# FPGA_Supply_Pins.net
KiCad netlist of a schematic drawn in Altium Designer
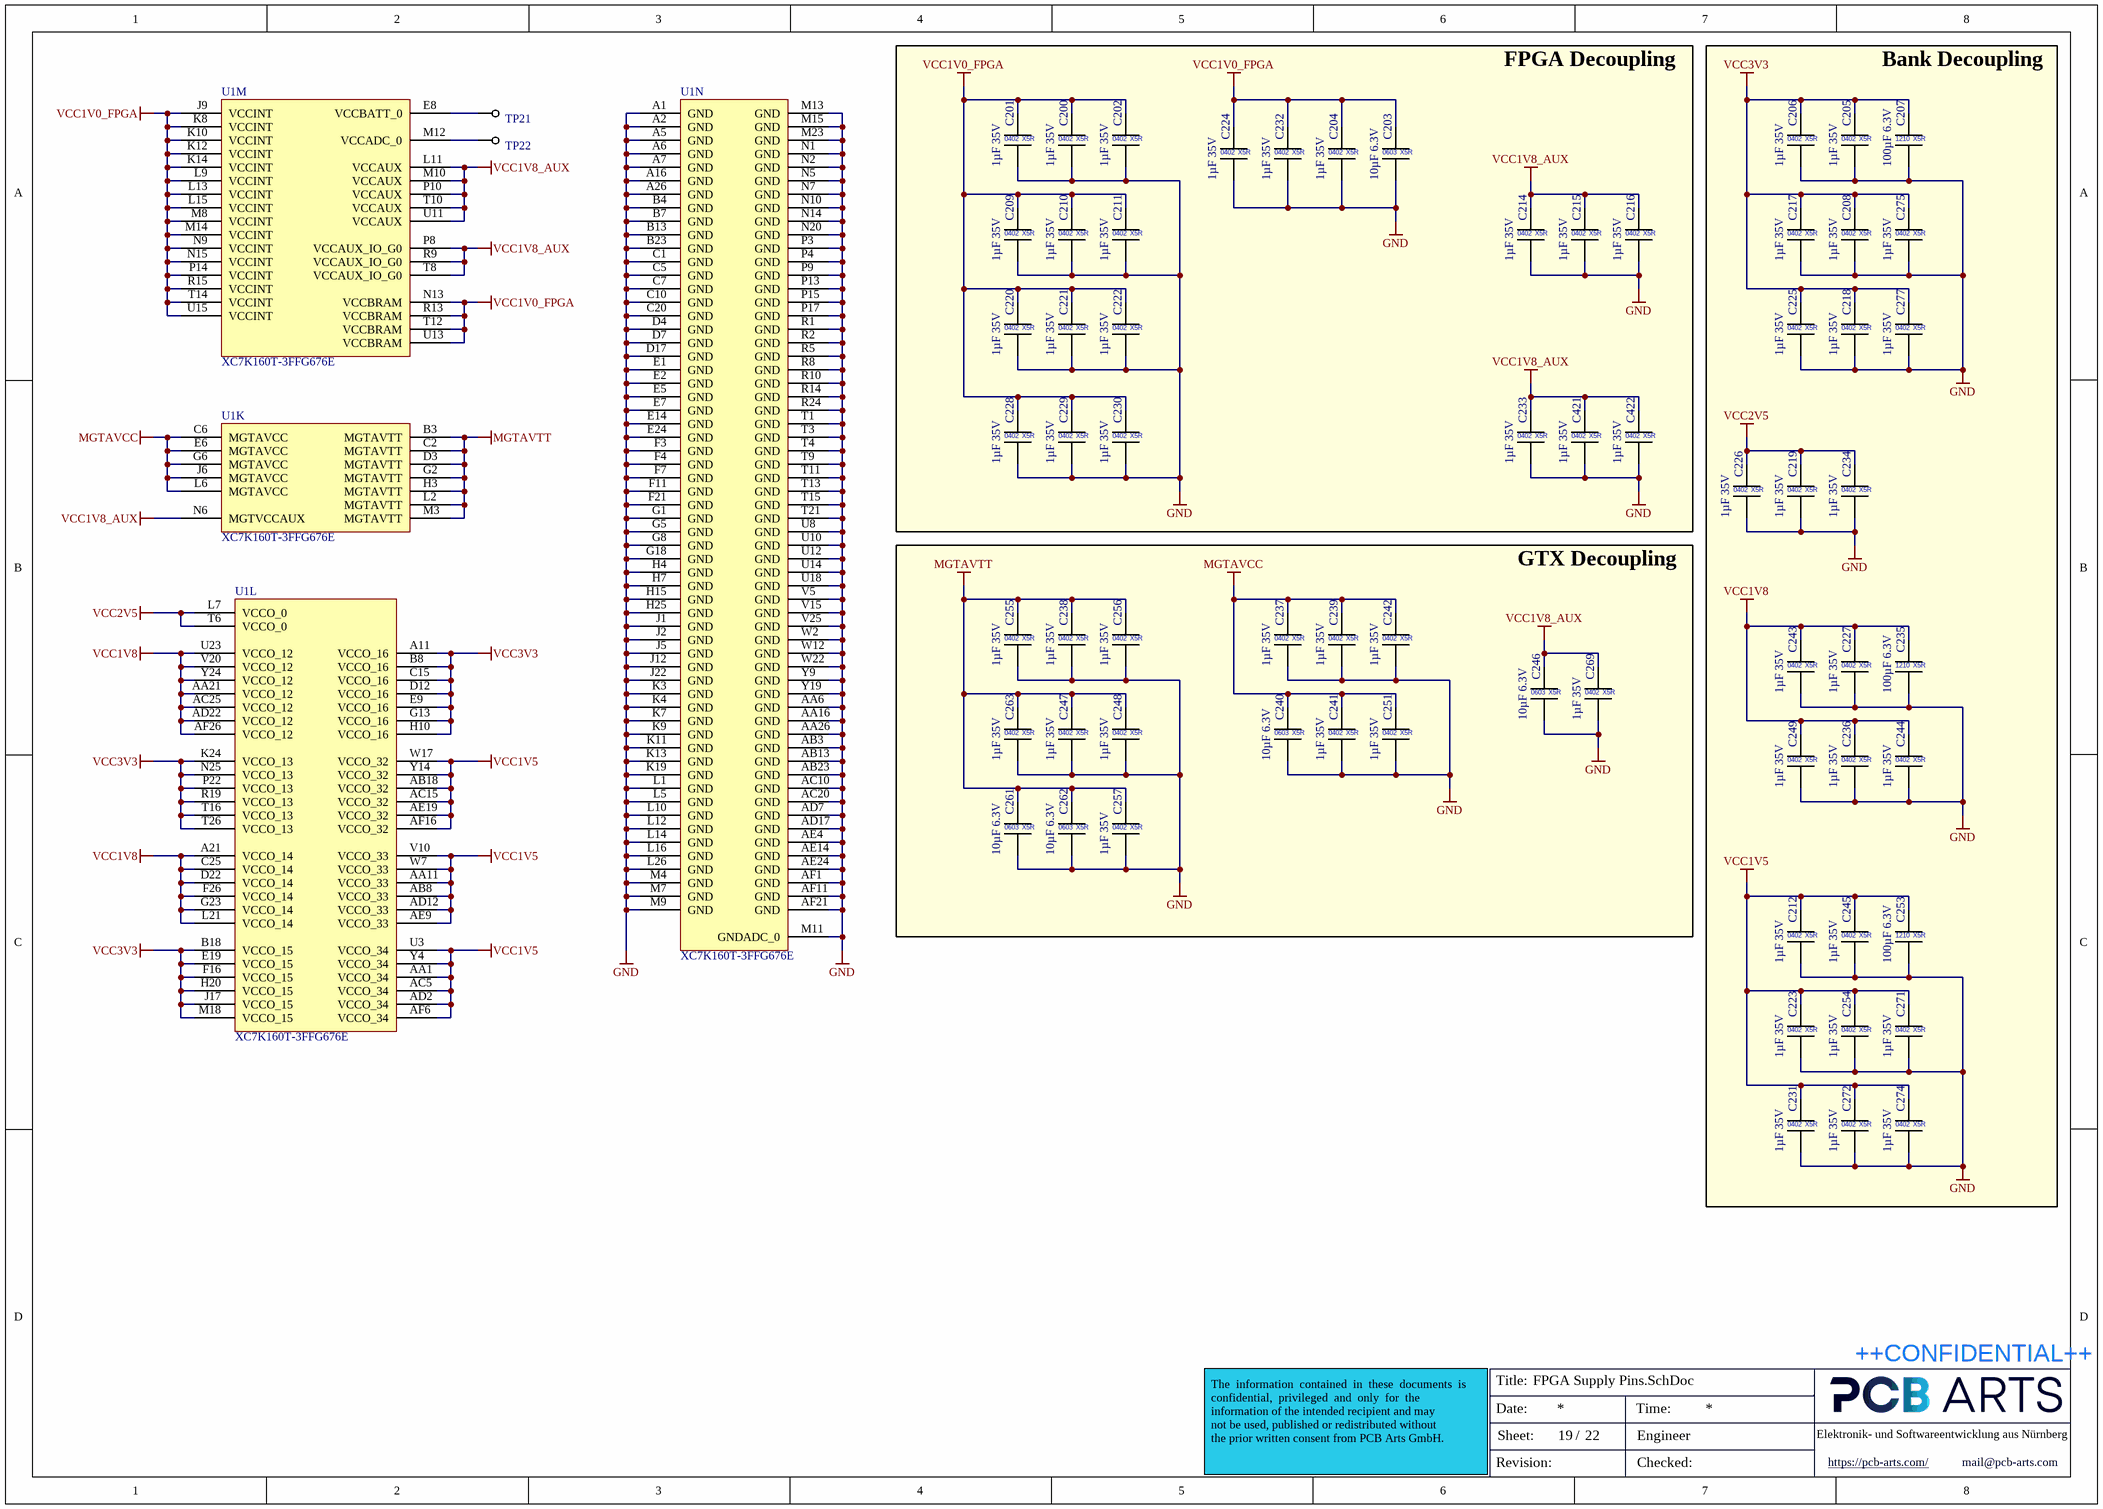
[diagram p0: FPGA Supply Pins.SchDoc]

(export (version "E")
  (design (tool "Eeschema 10.0.6"))
  (components
    (comp (ref "C200")
      (value "1µF 35V")
      (footprint "Cap:CAP_0402_L")
      (description "Multilayer Ceramic Capacitors MLCC - SMD/SMT 0402 35VDC")
      (libsource (lib "Cap") (part "CAP_0402_1µF_35V"))
    )
    (comp (ref "C201")
      (value "1µF 35V")
      (footprint "Cap:CAP_0402_L")
      (description "Multilayer Ceramic Capacitors MLCC - SMD/SMT 0402 35VDC")
      (libsource (lib "Cap") (part "CAP_0402_1µF_35V"))
    )
    (comp (ref "C202")
      (value "1µF 35V")
      (footprint "Cap:CAP_0402_L")
      (description "Multilayer Ceramic Capacitors MLCC - SMD/SMT 0402 35VDC")
      (libsource (lib "Cap") (part "CAP_0402_1µF_35V"))
    )
    (comp (ref "C203")
      (value "10µF 6.3V")
      (footprint "Cap:CAP_0603_L")
      (description "Multilayer Ceramic Capacitors MLCC - SMD/SMT 0603 6.3VDC")
      (libsource (lib "Cap") (part "CAP_0603_10µF_6.3V"))
    )
    (comp (ref "C204")
      (value "1µF 35V")
      (footprint "Cap:CAP_0402_L")
      (description "Multilayer Ceramic Capacitors MLCC - SMD/SMT 0402 35VDC")
      (libsource (lib "Cap") (part "CAP_0402_1µF_35V"))
    )
    (comp (ref "C205")
      (value "1µF 35V")
      (footprint "Cap:CAP_0402_L")
      (description "Multilayer Ceramic Capacitors MLCC - SMD/SMT 0402 35VDC")
      (libsource (lib "Cap") (part "CAP_0402_1µF_35V"))
    )
    (comp (ref "C206")
      (value "1µF 35V")
      (footprint "Cap:CAP_0402_L")
      (description "Multilayer Ceramic Capacitors MLCC - SMD/SMT 0402 35VDC")
      (libsource (lib "Cap") (part "CAP_0402_1µF_35V"))
    )
    (comp (ref "C207")
      (value "100µF 6.3V")
      (footprint "Cap:CAP_1210")
      (description "Multilayer Ceramic Capacitors MLCC - SMD/SMT 1210 6.3VDC")
      (libsource (lib "Cap") (part "CAP_1210_100µF_6.3V"))
    )
    (comp (ref "C208")
      (value "1µF 35V")
      (footprint "Cap:CAP_0402_L")
      (description "Multilayer Ceramic Capacitors MLCC - SMD/SMT 0402 35VDC")
      (libsource (lib "Cap") (part "CAP_0402_1µF_35V"))
    )
    (comp (ref "C209")
      (value "1µF 35V")
      (footprint "Cap:CAP_0402_L")
      (description "Multilayer Ceramic Capacitors MLCC - SMD/SMT 0402 35VDC")
      (libsource (lib "Cap") (part "CAP_0402_1µF_35V"))
    )
    (comp (ref "C210")
      (value "1µF 35V")
      (footprint "Cap:CAP_0402_L")
      (description "Multilayer Ceramic Capacitors MLCC - SMD/SMT 0402 35VDC")
      (libsource (lib "Cap") (part "CAP_0402_1µF_35V"))
    )
    (comp (ref "C211")
      (value "1µF 35V")
      (footprint "Cap:CAP_0402_L")
      (description "Multilayer Ceramic Capacitors MLCC - SMD/SMT 0402 35VDC")
      (libsource (lib "Cap") (part "CAP_0402_1µF_35V"))
    )
    (comp (ref "C212")
      (value "1µF 35V")
      (footprint "Cap:CAP_0402_L")
      (description "Multilayer Ceramic Capacitors MLCC - SMD/SMT 0402 35VDC")
      (libsource (lib "Cap") (part "CAP_0402_1µF_35V"))
    )
    (comp (ref "C214")
      (value "1µF 35V")
      (footprint "Cap:CAP_0402_L")
      (description "Multilayer Ceramic Capacitors MLCC - SMD/SMT 0402 35VDC")
      (libsource (lib "Cap") (part "CAP_0402_1µF_35V"))
    )
    (comp (ref "C215")
      (value "1µF 35V")
      (footprint "Cap:CAP_0402_L")
      (description "Multilayer Ceramic Capacitors MLCC - SMD/SMT 0402 35VDC")
      (libsource (lib "Cap") (part "CAP_0402_1µF_35V"))
    )
    (comp (ref "C216")
      (value "1µF 35V")
      (footprint "Cap:CAP_0402_L")
      (description "Multilayer Ceramic Capacitors MLCC - SMD/SMT 0402 35VDC")
      (libsource (lib "Cap") (part "CAP_0402_1µF_35V"))
    )
    (comp (ref "C217")
      (value "1µF 35V")
      (footprint "Cap:CAP_0402_L")
      (description "Multilayer Ceramic Capacitors MLCC - SMD/SMT 0402 35VDC")
      (libsource (lib "Cap") (part "CAP_0402_1µF_35V"))
    )
    (comp (ref "C218")
      (value "1µF 35V")
      (footprint "Cap:CAP_0402_L")
      (description "Multilayer Ceramic Capacitors MLCC - SMD/SMT 0402 35VDC")
      (libsource (lib "Cap") (part "CAP_0402_1µF_35V"))
    )
    (comp (ref "C219")
      (value "1µF 35V")
      (footprint "Cap:CAP_0402_L")
      (description "Multilayer Ceramic Capacitors MLCC - SMD/SMT 0402 35VDC")
      (libsource (lib "Cap") (part "CAP_0402_1µF_35V"))
    )
    (comp (ref "C220")
      (value "1µF 35V")
      (footprint "Cap:CAP_0402_L")
      (description "Multilayer Ceramic Capacitors MLCC - SMD/SMT 0402 35VDC")
      (libsource (lib "Cap") (part "CAP_0402_1µF_35V"))
    )
    (comp (ref "C221")
      (value "1µF 35V")
      (footprint "Cap:CAP_0402_L")
      (description "Multilayer Ceramic Capacitors MLCC - SMD/SMT 0402 35VDC")
      (libsource (lib "Cap") (part "CAP_0402_1µF_35V"))
    )
    (comp (ref "C222")
      (value "1µF 35V")
      (footprint "Cap:CAP_0402_L")
      (description "Multilayer Ceramic Capacitors MLCC - SMD/SMT 0402 35VDC")
      (libsource (lib "Cap") (part "CAP_0402_1µF_35V"))
    )
    (comp (ref "C223")
      (value "1µF 35V")
      (footprint "Cap:CAP_0402_L")
      (description "Multilayer Ceramic Capacitors MLCC - SMD/SMT 0402 35VDC")
      (libsource (lib "Cap") (part "CAP_0402_1µF_35V"))
    )
    (comp (ref "C224")
      (value "1µF 35V")
      (footprint "Cap:CAP_0402_L")
      (description "Multilayer Ceramic Capacitors MLCC - SMD/SMT 0402 35VDC")
      (libsource (lib "Cap") (part "CAP_0402_1µF_35V"))
    )
    (comp (ref "C225")
      (value "1µF 35V")
      (footprint "Cap:CAP_0402_L")
      (description "Multilayer Ceramic Capacitors MLCC - SMD/SMT 0402 35VDC")
      (libsource (lib "Cap") (part "CAP_0402_1µF_35V"))
    )
    (comp (ref "C226")
      (value "1µF 35V")
      (footprint "Cap:CAP_0402_L")
      (description "Multilayer Ceramic Capacitors MLCC - SMD/SMT 0402 35VDC")
      (libsource (lib "Cap") (part "CAP_0402_1µF_35V"))
    )
    (comp (ref "C227")
      (value "1µF 35V")
      (footprint "Cap:CAP_0402_L")
      (description "Multilayer Ceramic Capacitors MLCC - SMD/SMT 0402 35VDC")
      (libsource (lib "Cap") (part "CAP_0402_1µF_35V"))
    )
    (comp (ref "C228")
      (value "1µF 35V")
      (footprint "Cap:CAP_0402_L")
      (description "Multilayer Ceramic Capacitors MLCC - SMD/SMT 0402 35VDC")
      (libsource (lib "Cap") (part "CAP_0402_1µF_35V"))
    )
    (comp (ref "C229")
      (value "1µF 35V")
      (footprint "Cap:CAP_0402_L")
      (description "Multilayer Ceramic Capacitors MLCC - SMD/SMT 0402 35VDC")
      (libsource (lib "Cap") (part "CAP_0402_1µF_35V"))
    )
    (comp (ref "C230")
      (value "1µF 35V")
      (footprint "Cap:CAP_0402_L")
      (description "Multilayer Ceramic Capacitors MLCC - SMD/SMT 0402 35VDC")
      (libsource (lib "Cap") (part "CAP_0402_1µF_35V"))
    )
    (comp (ref "C231")
      (value "1µF 35V")
      (footprint "Cap:CAP_0402_L")
      (description "Multilayer Ceramic Capacitors MLCC - SMD/SMT 0402 35VDC")
      (libsource (lib "Cap") (part "CAP_0402_1µF_35V"))
    )
    (comp (ref "C232")
      (value "1µF 35V")
      (footprint "Cap:CAP_0402_L")
      (description "Multilayer Ceramic Capacitors MLCC - SMD/SMT 0402 35VDC")
      (libsource (lib "Cap") (part "CAP_0402_1µF_35V"))
    )
    (comp (ref "C233")
      (value "1µF 35V")
      (footprint "Cap:CAP_0402_L")
      (description "Multilayer Ceramic Capacitors MLCC - SMD/SMT 0402 35VDC")
      (libsource (lib "Cap") (part "CAP_0402_1µF_35V"))
    )
    (comp (ref "C234")
      (value "1µF 35V")
      (footprint "Cap:CAP_0402_L")
      (description "Multilayer Ceramic Capacitors MLCC - SMD/SMT 0402 35VDC")
      (libsource (lib "Cap") (part "CAP_0402_1µF_35V"))
    )
    (comp (ref "C235")
      (value "100µF 6.3V")
      (footprint "Cap:CAP_1210")
      (description "Multilayer Ceramic Capacitors MLCC - SMD/SMT 1210 6.3VDC")
      (libsource (lib "Cap") (part "CAP_1210_100µF_6.3V"))
    )
    (comp (ref "C236")
      (value "1µF 35V")
      (footprint "Cap:CAP_0402_L")
      (description "Multilayer Ceramic Capacitors MLCC - SMD/SMT 0402 35VDC")
      (libsource (lib "Cap") (part "CAP_0402_1µF_35V"))
    )
    (comp (ref "C237")
      (value "1µF 35V")
      (footprint "Cap:CAP_0402_L")
      (description "Multilayer Ceramic Capacitors MLCC - SMD/SMT 0402 35VDC")
      (libsource (lib "Cap") (part "CAP_0402_1µF_35V"))
    )
    (comp (ref "C238")
      (value "1µF 35V")
      (footprint "Cap:CAP_0402_L")
      (description "Multilayer Ceramic Capacitors MLCC - SMD/SMT 0402 35VDC")
      (libsource (lib "Cap") (part "CAP_0402_1µF_35V"))
    )
    (comp (ref "C239")
      (value "1µF 35V")
      (footprint "Cap:CAP_0402_L")
      (description "Multilayer Ceramic Capacitors MLCC - SMD/SMT 0402 35VDC")
      (libsource (lib "Cap") (part "CAP_0402_1µF_35V"))
    )
    (comp (ref "C240")
      (value "10µF 6.3V")
      (footprint "Cap:CAP_0603_L")
      (description "Multilayer Ceramic Capacitors MLCC - SMD/SMT 0603 6.3VDC")
      (libsource (lib "Cap") (part "CAP_0603_10µF_6.3V"))
    )
    (comp (ref "C241")
      (value "1µF 35V")
      (footprint "Cap:CAP_0402_L")
      (description "Multilayer Ceramic Capacitors MLCC - SMD/SMT 0402 35VDC")
      (libsource (lib "Cap") (part "CAP_0402_1µF_35V"))
    )
    (comp (ref "C242")
      (value "1µF 35V")
      (footprint "Cap:CAP_0402_L")
      (description "Multilayer Ceramic Capacitors MLCC - SMD/SMT 0402 35VDC")
      (libsource (lib "Cap") (part "CAP_0402_1µF_35V"))
    )
    (comp (ref "C243")
      (value "1µF 35V")
      (footprint "Cap:CAP_0402_L")
      (description "Multilayer Ceramic Capacitors MLCC - SMD/SMT 0402 35VDC")
      (libsource (lib "Cap") (part "CAP_0402_1µF_35V"))
    )
    (comp (ref "C244")
      (value "1µF 35V")
      (footprint "Cap:CAP_0402_L")
      (description "Multilayer Ceramic Capacitors MLCC - SMD/SMT 0402 35VDC")
      (libsource (lib "Cap") (part "CAP_0402_1µF_35V"))
    )
    (comp (ref "C245")
      (value "1µF 35V")
      (footprint "Cap:CAP_0402_L")
      (description "Multilayer Ceramic Capacitors MLCC - SMD/SMT 0402 35VDC")
      (libsource (lib "Cap") (part "CAP_0402_1µF_35V"))
    )
    (comp (ref "C246")
      (value "10µF 6.3V")
      (footprint "Cap:CAP_0603_L")
      (description "Multilayer Ceramic Capacitors MLCC - SMD/SMT 0603 6.3VDC")
      (libsource (lib "Cap") (part "CAP_0603_10µF_6.3V"))
    )
    (comp (ref "C247")
      (value "1µF 35V")
      (footprint "Cap:CAP_0402_L")
      (description "Multilayer Ceramic Capacitors MLCC - SMD/SMT 0402 35VDC")
      (libsource (lib "Cap") (part "CAP_0402_1µF_35V"))
    )
    (comp (ref "C248")
      (value "1µF 35V")
      (footprint "Cap:CAP_0402_L")
      (description "Multilayer Ceramic Capacitors MLCC - SMD/SMT 0402 35VDC")
      (libsource (lib "Cap") (part "CAP_0402_1µF_35V"))
    )
    (comp (ref "C249")
      (value "1µF 35V")
      (footprint "Cap:CAP_0402_L")
      (description "Multilayer Ceramic Capacitors MLCC - SMD/SMT 0402 35VDC")
      (libsource (lib "Cap") (part "CAP_0402_1µF_35V"))
    )
    (comp (ref "C251")
      (value "1µF 35V")
      (footprint "Cap:CAP_0402_L")
      (description "Multilayer Ceramic Capacitors MLCC - SMD/SMT 0402 35VDC")
      (libsource (lib "Cap") (part "CAP_0402_1µF_35V"))
    )
    (comp (ref "C253")
      (value "100µF 6.3V")
      (footprint "Cap:CAP_1210")
      (description "Multilayer Ceramic Capacitors MLCC - SMD/SMT 1210 6.3VDC")
      (libsource (lib "Cap") (part "CAP_1210_100µF_6.3V"))
    )
    (comp (ref "C254")
      (value "1µF 35V")
      (footprint "Cap:CAP_0402_L")
      (description "Multilayer Ceramic Capacitors MLCC - SMD/SMT 0402 35VDC")
      (libsource (lib "Cap") (part "CAP_0402_1µF_35V"))
    )
    (comp (ref "C255")
      (value "1µF 35V")
      (footprint "Cap:CAP_0402_L")
      (description "Multilayer Ceramic Capacitors MLCC - SMD/SMT 0402 35VDC")
      (libsource (lib "Cap") (part "CAP_0402_1µF_35V"))
    )
    (comp (ref "C256")
      (value "1µF 35V")
      (footprint "Cap:CAP_0402_L")
      (description "Multilayer Ceramic Capacitors MLCC - SMD/SMT 0402 35VDC")
      (libsource (lib "Cap") (part "CAP_0402_1µF_35V"))
    )
    (comp (ref "C257")
      (value "1µF 35V")
      (footprint "Cap:CAP_0402_L")
      (description "Multilayer Ceramic Capacitors MLCC - SMD/SMT 0402 35VDC")
      (libsource (lib "Cap") (part "CAP_0402_1µF_35V"))
    )
    (comp (ref "C261")
      (value "10µF 6.3V")
      (footprint "Cap:CAP_0603_L")
      (description "Multilayer Ceramic Capacitors MLCC - SMD/SMT 0603 6.3VDC")
      (libsource (lib "Cap") (part "CAP_0603_10µF_6.3V"))
    )
    (comp (ref "C262")
      (value "10µF 6.3V")
      (footprint "Cap:CAP_0603_L")
      (description "Multilayer Ceramic Capacitors MLCC - SMD/SMT 0603 6.3VDC")
      (libsource (lib "Cap") (part "CAP_0603_10µF_6.3V"))
    )
    (comp (ref "C263")
      (value "1µF 35V")
      (footprint "Cap:CAP_0402_L")
      (description "Multilayer Ceramic Capacitors MLCC - SMD/SMT 0402 35VDC")
      (libsource (lib "Cap") (part "CAP_0402_1µF_35V"))
    )
    (comp (ref "C269")
      (value "1µF 35V")
      (footprint "Cap:CAP_0402_L")
      (description "Multilayer Ceramic Capacitors MLCC - SMD/SMT 0402 35VDC")
      (libsource (lib "Cap") (part "CAP_0402_1µF_35V"))
    )
    (comp (ref "C271")
      (value "1µF 35V")
      (footprint "Cap:CAP_0402_L")
      (description "Multilayer Ceramic Capacitors MLCC - SMD/SMT 0402 35VDC")
      (libsource (lib "Cap") (part "CAP_0402_1µF_35V"))
    )
    (comp (ref "C272")
      (value "1µF 35V")
      (footprint "Cap:CAP_0402_L")
      (description "Multilayer Ceramic Capacitors MLCC - SMD/SMT 0402 35VDC")
      (libsource (lib "Cap") (part "CAP_0402_1µF_35V"))
    )
    (comp (ref "C274")
      (value "1µF 35V")
      (footprint "Cap:CAP_0402_L")
      (description "Multilayer Ceramic Capacitors MLCC - SMD/SMT 0402 35VDC")
      (libsource (lib "Cap") (part "CAP_0402_1µF_35V"))
    )
    (comp (ref "C275")
      (value "1µF 35V")
      (footprint "Cap:CAP_0402_L")
      (description "Multilayer Ceramic Capacitors MLCC - SMD/SMT 0402 35VDC")
      (libsource (lib "Cap") (part "CAP_0402_1µF_35V"))
    )
    (comp (ref "C277")
      (value "1µF 35V")
      (footprint "Cap:CAP_0402_L")
      (description "Multilayer Ceramic Capacitors MLCC - SMD/SMT 0402 35VDC")
      (libsource (lib "Cap") (part "CAP_0402_1µF_35V"))
    )
    (comp (ref "C421")
      (value "1µF 35V")
      (footprint "Cap:CAP_0402_L")
      (description "Multilayer Ceramic Capacitors MLCC - SMD/SMT 0402 35VDC")
      (libsource (lib "Cap") (part "CAP_0402_1µF_35V"))
    )
    (comp (ref "C422")
      (value "1µF 35V")
      (footprint "Cap:CAP_0402_L")
      (description "Multilayer Ceramic Capacitors MLCC - SMD/SMT 0402 35VDC")
      (libsource (lib "Cap") (part "CAP_0402_1µF_35V"))
    )
    (comp (ref "TP21")
      (value "Testpoint")
      (footprint "Electro_mech:Testpoint 0.8mm")
      (description "Testpoint 0.8mm")
      (libsource (lib "Electro_Mech") (part "Testpoint 0.8mm"))
    )
    (comp (ref "TP22")
      (value "Testpoint")
      (footprint "Electro_mech:Testpoint 0.8mm")
      (description "Testpoint 0.8mm")
      (libsource (lib "Electro_Mech") (part "Testpoint 0.8mm"))
    )
    (comp (ref "U1")
      (value "XC7K160T-3FFG676E")
      (footprint "Digital:BGA100P2700X2700X317-676N")
      (description "Kintex-7 FPGA, 400 User I/Os, 8 GTX, 676-Ball BGA, Speed Grade 3, Extended Grade, Pb-Free")
      (libsource (lib "Digital") (part "XC7K160T-3FFG676E_Kintex-7 FPGA, 400 User I/Os, 8 GTX, FFG676"))
    )
  )
  (nets
    (net (code "1") (name "GND") (class "Default")
      (node (ref "C200") (pin "2") (pinfunction "2_2") (pintype "passive"))
      (node (ref "C201") (pin "2") (pinfunction "2_2") (pintype "passive"))
      (node (ref "C202") (pin "2") (pinfunction "2_2") (pintype "passive"))
      (node (ref "C203") (pin "2") (pinfunction "2_2") (pintype "passive"))
      (node (ref "C204") (pin "2") (pinfunction "2_2") (pintype "passive"))
      (node (ref "C205") (pin "2") (pinfunction "2_2") (pintype "passive"))
      (node (ref "C206") (pin "2") (pinfunction "2_2") (pintype "passive"))
      (node (ref "C207") (pin "2") (pinfunction "2_2") (pintype "passive"))
      (node (ref "C208") (pin "2") (pinfunction "2_2") (pintype "passive"))
      (node (ref "C209") (pin "2") (pinfunction "2_2") (pintype "passive"))
      (node (ref "C210") (pin "2") (pinfunction "2_2") (pintype "passive"))
      (node (ref "C211") (pin "2") (pinfunction "2_2") (pintype "passive"))
      (node (ref "C212") (pin "2") (pinfunction "2_2") (pintype "passive"))
      (node (ref "C214") (pin "2") (pinfunction "2_2") (pintype "passive"))
      (node (ref "C215") (pin "2") (pinfunction "2_2") (pintype "passive"))
      (node (ref "C216") (pin "2") (pinfunction "2_2") (pintype "passive"))
      (node (ref "C217") (pin "2") (pinfunction "2_2") (pintype "passive"))
      (node (ref "C218") (pin "2") (pinfunction "2_2") (pintype "passive"))
      (node (ref "C219") (pin "2") (pinfunction "2_2") (pintype "passive"))
      (node (ref "C220") (pin "2") (pinfunction "2_2") (pintype "passive"))
      (node (ref "C221") (pin "2") (pinfunction "2_2") (pintype "passive"))
      (node (ref "C222") (pin "2") (pinfunction "2_2") (pintype "passive"))
      (node (ref "C223") (pin "2") (pinfunction "2_2") (pintype "passive"))
      (node (ref "C224") (pin "2") (pinfunction "2_2") (pintype "passive"))
      (node (ref "C225") (pin "2") (pinfunction "2_2") (pintype "passive"))
      (node (ref "C226") (pin "2") (pinfunction "2_2") (pintype "passive"))
      (node (ref "C227") (pin "2") (pinfunction "2_2") (pintype "passive"))
      (node (ref "C228") (pin "2") (pinfunction "2_2") (pintype "passive"))
      (node (ref "C229") (pin "2") (pinfunction "2_2") (pintype "passive"))
      (node (ref "C230") (pin "2") (pinfunction "2_2") (pintype "passive"))
      (node (ref "C231") (pin "2") (pinfunction "2_2") (pintype "passive"))
      (node (ref "C232") (pin "2") (pinfunction "2_2") (pintype "passive"))
      (node (ref "C233") (pin "2") (pinfunction "2_2") (pintype "passive"))
      (node (ref "C234") (pin "2") (pinfunction "2_2") (pintype "passive"))
      (node (ref "C235") (pin "2") (pinfunction "2_2") (pintype "passive"))
      (node (ref "C236") (pin "2") (pinfunction "2_2") (pintype "passive"))
      (node (ref "C237") (pin "2") (pinfunction "2_2") (pintype "passive"))
      (node (ref "C238") (pin "2") (pinfunction "2_2") (pintype "passive"))
      (node (ref "C239") (pin "2") (pinfunction "2_2") (pintype "passive"))
      (node (ref "C240") (pin "2") (pinfunction "2_2") (pintype "passive"))
      (node (ref "C241") (pin "2") (pinfunction "2_2") (pintype "passive"))
      (node (ref "C242") (pin "2") (pinfunction "2_2") (pintype "passive"))
      (node (ref "C243") (pin "2") (pinfunction "2_2") (pintype "passive"))
      (node (ref "C244") (pin "2") (pinfunction "2_2") (pintype "passive"))
      (node (ref "C245") (pin "2") (pinfunction "2_2") (pintype "passive"))
      (node (ref "C246") (pin "2") (pinfunction "2_2") (pintype "passive"))
      (node (ref "C247") (pin "2") (pinfunction "2_2") (pintype "passive"))
      (node (ref "C248") (pin "2") (pinfunction "2_2") (pintype "passive"))
      (node (ref "C249") (pin "2") (pinfunction "2_2") (pintype "passive"))
      (node (ref "C251") (pin "2") (pinfunction "2_2") (pintype "passive"))
      (node (ref "C253") (pin "2") (pinfunction "2_2") (pintype "passive"))
      (node (ref "C254") (pin "2") (pinfunction "2_2") (pintype "passive"))
      (node (ref "C255") (pin "2") (pinfunction "2_2") (pintype "passive"))
      (node (ref "C256") (pin "2") (pinfunction "2_2") (pintype "passive"))
      (node (ref "C257") (pin "2") (pinfunction "2_2") (pintype "passive"))
      (node (ref "C261") (pin "2") (pinfunction "2_2") (pintype "passive"))
      (node (ref "C262") (pin "2") (pinfunction "2_2") (pintype "passive"))
      (node (ref "C263") (pin "2") (pinfunction "2_2") (pintype "passive"))
      (node (ref "C269") (pin "2") (pinfunction "2_2") (pintype "passive"))
      (node (ref "C271") (pin "2") (pinfunction "2_2") (pintype "passive"))
      (node (ref "C272") (pin "2") (pinfunction "2_2") (pintype "passive"))
      (node (ref "C274") (pin "2") (pinfunction "2_2") (pintype "passive"))
      (node (ref "C275") (pin "2") (pinfunction "2_2") (pintype "passive"))
      (node (ref "C277") (pin "2") (pinfunction "2_2") (pintype "passive"))
      (node (ref "C421") (pin "2") (pinfunction "2_2") (pintype "passive"))
      (node (ref "C422") (pin "2") (pinfunction "2_2") (pintype "passive"))
      (node (ref "U1") (pin "A1") (pinfunction "GND_A1") (pintype "power_in"))
      (node (ref "U1") (pin "A16") (pinfunction "GND_A16") (pintype "power_in"))
      (node (ref "U1") (pin "A2") (pinfunction "GND_A2") (pintype "power_in"))
      (node (ref "U1") (pin "A26") (pinfunction "GND_A26") (pintype "power_in"))
      (node (ref "U1") (pin "A5") (pinfunction "GND_A5") (pintype "power_in"))
      (node (ref "U1") (pin "A6") (pinfunction "GND_A6") (pintype "power_in"))
      (node (ref "U1") (pin "A7") (pinfunction "GND_A7") (pintype "power_in"))
      (node (ref "U1") (pin "AA16") (pinfunction "GND_AA16") (pintype "power_in"))
      (node (ref "U1") (pin "AA26") (pinfunction "GND_AA26") (pintype "power_in"))
      (node (ref "U1") (pin "AA6") (pinfunction "GND_AA6") (pintype "power_in"))
      (node (ref "U1") (pin "AB13") (pinfunction "GND_AB13") (pintype "power_in"))
      (node (ref "U1") (pin "AB23") (pinfunction "GND_AB23") (pintype "power_in"))
      (node (ref "U1") (pin "AB3") (pinfunction "GND_AB3") (pintype "power_in"))
      (node (ref "U1") (pin "AC10") (pinfunction "GND_AC10") (pintype "power_in"))
      (node (ref "U1") (pin "AC20") (pinfunction "GND_AC20") (pintype "power_in"))
      (node (ref "U1") (pin "AD17") (pinfunction "GND_AD17") (pintype "power_in"))
      (node (ref "U1") (pin "AD7") (pinfunction "GND_AD7") (pintype "power_in"))
      (node (ref "U1") (pin "AE14") (pinfunction "GND_AE14") (pintype "power_in"))
      (node (ref "U1") (pin "AE24") (pinfunction "GND_AE24") (pintype "power_in"))
      (node (ref "U1") (pin "AE4") (pinfunction "GND_AE4") (pintype "power_in"))
      (node (ref "U1") (pin "AF1") (pinfunction "GND_AF1") (pintype "power_in"))
      (node (ref "U1") (pin "AF11") (pinfunction "GND_AF11") (pintype "power_in"))
      (node (ref "U1") (pin "AF21") (pinfunction "GND_AF21") (pintype "power_in"))
      (node (ref "U1") (pin "B13") (pinfunction "GND_B13") (pintype "power_in"))
      (node (ref "U1") (pin "B23") (pinfunction "GND_B23") (pintype "power_in"))
      (node (ref "U1") (pin "B4") (pinfunction "GND_B4") (pintype "power_in"))
      (node (ref "U1") (pin "B7") (pinfunction "GND_B7") (pintype "power_in"))
      (node (ref "U1") (pin "C1") (pinfunction "GND_C1") (pintype "power_in"))
      (node (ref "U1") (pin "C10") (pinfunction "GND_C10") (pintype "power_in"))
      (node (ref "U1") (pin "C20") (pinfunction "GND_C20") (pintype "power_in"))
      (node (ref "U1") (pin "C5") (pinfunction "GND_C5") (pintype "power_in"))
      (node (ref "U1") (pin "C7") (pinfunction "GND_C7") (pintype "power_in"))
      (node (ref "U1") (pin "D17") (pinfunction "GND_D17") (pintype "power_in"))
      (node (ref "U1") (pin "D4") (pinfunction "GND_D4") (pintype "power_in"))
      (node (ref "U1") (pin "D7") (pinfunction "GND_D7") (pintype "power_in"))
      (node (ref "U1") (pin "E1") (pinfunction "GND_E1") (pintype "power_in"))
      (node (ref "U1") (pin "E14") (pinfunction "GND_E14") (pintype "power_in"))
      (node (ref "U1") (pin "E2") (pinfunction "GND_E2") (pintype "power_in"))
      (node (ref "U1") (pin "E24") (pinfunction "GND_E24") (pintype "power_in"))
      (node (ref "U1") (pin "E5") (pinfunction "GND_E5") (pintype "power_in"))
      (node (ref "U1") (pin "E7") (pinfunction "GND_E7") (pintype "power_in"))
      (node (ref "U1") (pin "F11") (pinfunction "GND_F11") (pintype "power_in"))
      (node (ref "U1") (pin "F21") (pinfunction "GND_F21") (pintype "power_in"))
      (node (ref "U1") (pin "F3") (pinfunction "GND_F3") (pintype "power_in"))
      (node (ref "U1") (pin "F4") (pinfunction "GND_F4") (pintype "power_in"))
      (node (ref "U1") (pin "F7") (pinfunction "GND_F7") (pintype "power_in"))
      (node (ref "U1") (pin "G1") (pinfunction "GND_G1") (pintype "power_in"))
      (node (ref "U1") (pin "G18") (pinfunction "GND_G18") (pintype "power_in"))
      (node (ref "U1") (pin "G5") (pinfunction "GND_G5") (pintype "power_in"))
      (node (ref "U1") (pin "G8") (pinfunction "GND_G8") (pintype "power_in"))
      (node (ref "U1") (pin "H15") (pinfunction "GND_H15") (pintype "power_in"))
      (node (ref "U1") (pin "H25") (pinfunction "GND_H25") (pintype "power_in"))
      (node (ref "U1") (pin "H4") (pinfunction "GND_H4") (pintype "power_in"))
      (node (ref "U1") (pin "H7") (pinfunction "GND_H7") (pintype "power_in"))
      (node (ref "U1") (pin "J1") (pinfunction "GND_J1") (pintype "power_in"))
      (node (ref "U1") (pin "J12") (pinfunction "GND_J12") (pintype "power_in"))
      (node (ref "U1") (pin "J2") (pinfunction "GND_J2") (pintype "power_in"))
      (node (ref "U1") (pin "J22") (pinfunction "GND_J22") (pintype "power_in"))
      (node (ref "U1") (pin "J5") (pinfunction "GND_J5") (pintype "power_in"))
      (node (ref "U1") (pin "K11") (pinfunction "GND_K11") (pintype "power_in"))
      (node (ref "U1") (pin "K13") (pinfunction "GND_K13") (pintype "power_in"))
      (node (ref "U1") (pin "K19") (pinfunction "GND_K19") (pintype "power_in"))
      (node (ref "U1") (pin "K3") (pinfunction "GND_K3") (pintype "power_in"))
      (node (ref "U1") (pin "K4") (pinfunction "GND_K4") (pintype "power_in"))
      (node (ref "U1") (pin "K7") (pinfunction "GND_K7") (pintype "power_in"))
      (node (ref "U1") (pin "K9") (pinfunction "GND_K9") (pintype "power_in"))
      (node (ref "U1") (pin "L1") (pinfunction "GND_L1") (pintype "power_in"))
      (node (ref "U1") (pin "L10") (pinfunction "GND_L10") (pintype "power_in"))
      (node (ref "U1") (pin "L12") (pinfunction "GND_L12") (pintype "power_in"))
      (node (ref "U1") (pin "L14") (pinfunction "GND_L14") (pintype "power_in"))
      (node (ref "U1") (pin "L16") (pinfunction "GND_L16") (pintype "power_in"))
      (node (ref "U1") (pin "L26") (pinfunction "GND_L26") (pintype "power_in"))
      (node (ref "U1") (pin "L5") (pinfunction "GND_L5") (pintype "power_in"))
      (node (ref "U1") (pin "M11") (pinfunction "GNDADC_0_M11") (pintype "power_in"))
      (node (ref "U1") (pin "M13") (pinfunction "GND_M13") (pintype "power_in"))
      (node (ref "U1") (pin "M15") (pinfunction "GND_M15") (pintype "power_in"))
      (node (ref "U1") (pin "M23") (pinfunction "GND_M23") (pintype "power_in"))
      (node (ref "U1") (pin "M4") (pinfunction "GND_M4") (pintype "power_in"))
      (node (ref "U1") (pin "M7") (pinfunction "GND_M7") (pintype "power_in"))
      (node (ref "U1") (pin "M9") (pinfunction "GND_M9") (pintype "power_in"))
      (node (ref "U1") (pin "N1") (pinfunction "GND_N1") (pintype "power_in"))
      (node (ref "U1") (pin "N10") (pinfunction "GND_N10") (pintype "power_in"))
      (node (ref "U1") (pin "N14") (pinfunction "GND_N14") (pintype "power_in"))
      (node (ref "U1") (pin "N2") (pinfunction "GND_N2") (pintype "power_in"))
      (node (ref "U1") (pin "N20") (pinfunction "GND_N20") (pintype "power_in"))
      (node (ref "U1") (pin "N5") (pinfunction "GND_N5") (pintype "power_in"))
      (node (ref "U1") (pin "N7") (pinfunction "GND_N7") (pintype "power_in"))
      (node (ref "U1") (pin "P13") (pinfunction "GND_P13") (pintype "power_in"))
      (node (ref "U1") (pin "P15") (pinfunction "GND_P15") (pintype "power_in"))
      (node (ref "U1") (pin "P17") (pinfunction "GND_P17") (pintype "power_in"))
      (node (ref "U1") (pin "P3") (pinfunction "GND_P3") (pintype "power_in"))
      (node (ref "U1") (pin "P4") (pinfunction "GND_P4") (pintype "power_in"))
      (node (ref "U1") (pin "P9") (pinfunction "GND_P9") (pintype "power_in"))
      (node (ref "U1") (pin "R1") (pinfunction "GND_R1") (pintype "power_in"))
      (node (ref "U1") (pin "R10") (pinfunction "GND_R10") (pintype "power_in"))
      (node (ref "U1") (pin "R14") (pinfunction "GND_R14") (pintype "power_in"))
      (node (ref "U1") (pin "R2") (pinfunction "GND_R2") (pintype "power_in"))
      (node (ref "U1") (pin "R24") (pinfunction "GND_R24") (pintype "power_in"))
      (node (ref "U1") (pin "R5") (pinfunction "GND_R5") (pintype "power_in"))
      (node (ref "U1") (pin "R8") (pinfunction "GND_R8") (pintype "power_in"))
      (node (ref "U1") (pin "T1") (pinfunction "GND_T1") (pintype "power_in"))
      (node (ref "U1") (pin "T11") (pinfunction "GND_T11") (pintype "power_in"))
      (node (ref "U1") (pin "T13") (pinfunction "GND_T13") (pintype "power_in"))
      (node (ref "U1") (pin "T15") (pinfunction "GND_T15") (pintype "power_in"))
      (node (ref "U1") (pin "T21") (pinfunction "GND_T21") (pintype "power_in"))
      (node (ref "U1") (pin "T3") (pinfunction "GND_T3") (pintype "power_in"))
      (node (ref "U1") (pin "T4") (pinfunction "GND_T4") (pintype "power_in"))
      (node (ref "U1") (pin "T9") (pinfunction "GND_T9") (pintype "power_in"))
      (node (ref "U1") (pin "U10") (pinfunction "GND_U10") (pintype "power_in"))
      (node (ref "U1") (pin "U12") (pinfunction "GND_U12") (pintype "power_in"))
      (node (ref "U1") (pin "U14") (pinfunction "GND_U14") (pintype "power_in"))
      (node (ref "U1") (pin "U18") (pinfunction "GND_U18") (pintype "power_in"))
      (node (ref "U1") (pin "U8") (pinfunction "GND_U8") (pintype "power_in"))
      (node (ref "U1") (pin "V15") (pinfunction "GND_V15") (pintype "power_in"))
      (node (ref "U1") (pin "V25") (pinfunction "GND_V25") (pintype "power_in"))
      (node (ref "U1") (pin "V5") (pinfunction "GND_V5") (pintype "power_in"))
      (node (ref "U1") (pin "W12") (pinfunction "GND_W12") (pintype "power_in"))
      (node (ref "U1") (pin "W2") (pinfunction "GND_W2") (pintype "power_in"))
      (node (ref "U1") (pin "W22") (pinfunction "GND_W22") (pintype "power_in"))
      (node (ref "U1") (pin "Y19") (pinfunction "GND_Y19") (pintype "power_in"))
      (node (ref "U1") (pin "Y9") (pinfunction "GND_Y9") (pintype "power_in"))
    )
    (net (code "2") (name "MGTAVCC") (class "Default")
      (node (ref "C237") (pin "1") (pinfunction "1_1") (pintype "passive"))
      (node (ref "C239") (pin "1") (pinfunction "1_1") (pintype "passive"))
      (node (ref "C240") (pin "1") (pinfunction "1_1") (pintype "passive"))
      (node (ref "C241") (pin "1") (pinfunction "1_1") (pintype "passive"))
      (node (ref "C242") (pin "1") (pinfunction "1_1") (pintype "passive"))
      (node (ref "C251") (pin "1") (pinfunction "1_1") (pintype "passive"))
      (node (ref "U1") (pin "C6") (pinfunction "MGTAVCC_C6") (pintype "power_in"))
      (node (ref "U1") (pin "E6") (pinfunction "MGTAVCC_E6") (pintype "power_in"))
      (node (ref "U1") (pin "G6") (pinfunction "MGTAVCC_G6") (pintype "power_in"))
      (node (ref "U1") (pin "J6") (pinfunction "MGTAVCC_J6") (pintype "power_in"))
      (node (ref "U1") (pin "L6") (pinfunction "MGTAVCC_L6") (pintype "power_in"))
    )
    (net (code "3") (name "MGTAVTT") (class "Default")
      (node (ref "C238") (pin "1") (pinfunction "1_1") (pintype "passive"))
      (node (ref "C247") (pin "1") (pinfunction "1_1") (pintype "passive"))
      (node (ref "C248") (pin "1") (pinfunction "1_1") (pintype "passive"))
      (node (ref "C255") (pin "1") (pinfunction "1_1") (pintype "passive"))
      (node (ref "C256") (pin "1") (pinfunction "1_1") (pintype "passive"))
      (node (ref "C257") (pin "1") (pinfunction "1_1") (pintype "passive"))
      (node (ref "C261") (pin "1") (pinfunction "1_1") (pintype "passive"))
      (node (ref "C262") (pin "1") (pinfunction "1_1") (pintype "passive"))
      (node (ref "C263") (pin "1") (pinfunction "1_1") (pintype "passive"))
      (node (ref "U1") (pin "B3") (pinfunction "MGTAVTT_B3") (pintype "power_in"))
      (node (ref "U1") (pin "C2") (pinfunction "MGTAVTT_C2") (pintype "power_in"))
      (node (ref "U1") (pin "D3") (pinfunction "MGTAVTT_D3") (pintype "power_in"))
      (node (ref "U1") (pin "G2") (pinfunction "MGTAVTT_G2") (pintype "power_in"))
      (node (ref "U1") (pin "H3") (pinfunction "MGTAVTT_H3") (pintype "power_in"))
      (node (ref "U1") (pin "L2") (pinfunction "MGTAVTT_L2") (pintype "power_in"))
      (node (ref "U1") (pin "M3") (pinfunction "MGTAVTT_M3") (pintype "power_in"))
    )
    (net (code "4") (name "Net-(TP21-GND)") (class "Default")
      (node (ref "TP21") (pin "1") (pinfunction "GND_1") (pintype "passive"))
      (node (ref "U1") (pin "E8") (pinfunction "VCCBATT_0_E8") (pintype "power_in"))
    )
    (net (code "5") (name "Net-(TP22-GND)") (class "Default")
      (node (ref "TP22") (pin "1") (pinfunction "GND_1") (pintype "passive"))
      (node (ref "U1") (pin "M12") (pinfunction "VCCADC_0_M12") (pintype "power_in"))
    )
    (net (code "6") (name "VCC1V0_FPGA") (class "Default")
      (node (ref "C200") (pin "1") (pinfunction "1_1") (pintype "passive"))
      (node (ref "C201") (pin "1") (pinfunction "1_1") (pintype "passive"))
      (node (ref "C202") (pin "1") (pinfunction "1_1") (pintype "passive"))
      (node (ref "C203") (pin "1") (pinfunction "1_1") (pintype "passive"))
      (node (ref "C204") (pin "1") (pinfunction "1_1") (pintype "passive"))
      (node (ref "C209") (pin "1") (pinfunction "1_1") (pintype "passive"))
      (node (ref "C210") (pin "1") (pinfunction "1_1") (pintype "passive"))
      (node (ref "C211") (pin "1") (pinfunction "1_1") (pintype "passive"))
      (node (ref "C220") (pin "1") (pinfunction "1_1") (pintype "passive"))
      (node (ref "C221") (pin "1") (pinfunction "1_1") (pintype "passive"))
      (node (ref "C222") (pin "1") (pinfunction "1_1") (pintype "passive"))
      (node (ref "C224") (pin "1") (pinfunction "1_1") (pintype "passive"))
      (node (ref "C228") (pin "1") (pinfunction "1_1") (pintype "passive"))
      (node (ref "C229") (pin "1") (pinfunction "1_1") (pintype "passive"))
      (node (ref "C230") (pin "1") (pinfunction "1_1") (pintype "passive"))
      (node (ref "C232") (pin "1") (pinfunction "1_1") (pintype "passive"))
      (node (ref "U1") (pin "J9") (pinfunction "VCCINT_J9") (pintype "power_in"))
      (node (ref "U1") (pin "K10") (pinfunction "VCCINT_K10") (pintype "power_in"))
      (node (ref "U1") (pin "K12") (pinfunction "VCCINT_K12") (pintype "power_in"))
      (node (ref "U1") (pin "K14") (pinfunction "VCCINT_K14") (pintype "power_in"))
      (node (ref "U1") (pin "K8") (pinfunction "VCCINT_K8") (pintype "power_in"))
      (node (ref "U1") (pin "L13") (pinfunction "VCCINT_L13") (pintype "power_in"))
      (node (ref "U1") (pin "L15") (pinfunction "VCCINT_L15") (pintype "power_in"))
      (node (ref "U1") (pin "L9") (pinfunction "VCCINT_L9") (pintype "power_in"))
      (node (ref "U1") (pin "M14") (pinfunction "VCCINT_M14") (pintype "power_in"))
      (node (ref "U1") (pin "M8") (pinfunction "VCCINT_M8") (pintype "power_in"))
      (node (ref "U1") (pin "N13") (pinfunction "VCCBRAM_N13") (pintype "power_in"))
      (node (ref "U1") (pin "N15") (pinfunction "VCCINT_N15") (pintype "power_in"))
      (node (ref "U1") (pin "N9") (pinfunction "VCCINT_N9") (pintype "power_in"))
      (node (ref "U1") (pin "P14") (pinfunction "VCCINT_P14") (pintype "power_in"))
      (node (ref "U1") (pin "R13") (pinfunction "VCCBRAM_R13") (pintype "power_in"))
      (node (ref "U1") (pin "R15") (pinfunction "VCCINT_R15") (pintype "power_in"))
      (node (ref "U1") (pin "T12") (pinfunction "VCCBRAM_T12") (pintype "power_in"))
      (node (ref "U1") (pin "T14") (pinfunction "VCCINT_T14") (pintype "power_in"))
      (node (ref "U1") (pin "U13") (pinfunction "VCCBRAM_U13") (pintype "power_in"))
      (node (ref "U1") (pin "U15") (pinfunction "VCCINT_U15") (pintype "power_in"))
    )
    (net (code "7") (name "VCC1V5") (class "Default")
      (node (ref "C212") (pin "1") (pinfunction "1_1") (pintype "passive"))
      (node (ref "C223") (pin "1") (pinfunction "1_1") (pintype "passive"))
      (node (ref "C231") (pin "1") (pinfunction "1_1") (pintype "passive"))
      (node (ref "C245") (pin "1") (pinfunction "1_1") (pintype "passive"))
      (node (ref "C253") (pin "1") (pinfunction "1_1") (pintype "passive"))
      (node (ref "C254") (pin "1") (pinfunction "1_1") (pintype "passive"))
      (node (ref "C271") (pin "1") (pinfunction "1_1") (pintype "passive"))
      (node (ref "C272") (pin "1") (pinfunction "1_1") (pintype "passive"))
      (node (ref "C274") (pin "1") (pinfunction "1_1") (pintype "passive"))
      (node (ref "U1") (pin "AA1") (pinfunction "VCCO_34_AA1") (pintype "power_in"))
      (node (ref "U1") (pin "AA11") (pinfunction "VCCO_33_AA11") (pintype "power_in"))
      (node (ref "U1") (pin "AB18") (pinfunction "VCCO_32_AB18") (pintype "power_in"))
      (node (ref "U1") (pin "AB8") (pinfunction "VCCO_33_AB8") (pintype "power_in"))
      (node (ref "U1") (pin "AC15") (pinfunction "VCCO_32_AC15") (pintype "power_in"))
      (node (ref "U1") (pin "AC5") (pinfunction "VCCO_34_AC5") (pintype "power_in"))
      (node (ref "U1") (pin "AD12") (pinfunction "VCCO_33_AD12") (pintype "power_in"))
      (node (ref "U1") (pin "AD2") (pinfunction "VCCO_34_AD2") (pintype "power_in"))
      (node (ref "U1") (pin "AE19") (pinfunction "VCCO_32_AE19") (pintype "power_in"))
      (node (ref "U1") (pin "AE9") (pinfunction "VCCO_33_AE9") (pintype "power_in"))
      (node (ref "U1") (pin "AF16") (pinfunction "VCCO_32_AF16") (pintype "power_in"))
      (node (ref "U1") (pin "AF6") (pinfunction "VCCO_34_AF6") (pintype "power_in"))
      (node (ref "U1") (pin "U3") (pinfunction "VCCO_34_U3") (pintype "power_in"))
      (node (ref "U1") (pin "V10") (pinfunction "VCCO_33_V10") (pintype "power_in"))
      (node (ref "U1") (pin "W17") (pinfunction "VCCO_32_W17") (pintype "power_in"))
      (node (ref "U1") (pin "W7") (pinfunction "VCCO_33_W7") (pintype "power_in"))
      (node (ref "U1") (pin "Y14") (pinfunction "VCCO_32_Y14") (pintype "power_in"))
      (node (ref "U1") (pin "Y4") (pinfunction "VCCO_34_Y4") (pintype "power_in"))
    )
    (net (code "8") (name "VCC1V8") (class "Default")
      (node (ref "C227") (pin "1") (pinfunction "1_1") (pintype "passive"))
      (node (ref "C235") (pin "1") (pinfunction "1_1") (pintype "passive"))
      (node (ref "C236") (pin "1") (pinfunction "1_1") (pintype "passive"))
      (node (ref "C243") (pin "1") (pinfunction "1_1") (pintype "passive"))
      (node (ref "C244") (pin "1") (pinfunction "1_1") (pintype "passive"))
      (node (ref "C249") (pin "1") (pinfunction "1_1") (pintype "passive"))
      (node (ref "U1") (pin "A21") (pinfunction "VCCO_14_A21") (pintype "power_in"))
      (node (ref "U1") (pin "AA21") (pinfunction "VCCO_12_AA21") (pintype "power_in"))
      (node (ref "U1") (pin "AC25") (pinfunction "VCCO_12_AC25") (pintype "power_in"))
      (node (ref "U1") (pin "AD22") (pinfunction "VCCO_12_AD22") (pintype "power_in"))
      (node (ref "U1") (pin "AF26") (pinfunction "VCCO_12_AF26") (pintype "power_in"))
      (node (ref "U1") (pin "C25") (pinfunction "VCCO_14_C25") (pintype "power_in"))
      (node (ref "U1") (pin "D22") (pinfunction "VCCO_14_D22") (pintype "power_in"))
      (node (ref "U1") (pin "F26") (pinfunction "VCCO_14_F26") (pintype "power_in"))
      (node (ref "U1") (pin "G23") (pinfunction "VCCO_14_G23") (pintype "power_in"))
      (node (ref "U1") (pin "L21") (pinfunction "VCCO_14_L21") (pintype "power_in"))
      (node (ref "U1") (pin "U23") (pinfunction "VCCO_12_U23") (pintype "power_in"))
      (node (ref "U1") (pin "V20") (pinfunction "VCCO_12_V20") (pintype "power_in"))
      (node (ref "U1") (pin "Y24") (pinfunction "VCCO_12_Y24") (pintype "power_in"))
    )
    (net (code "9") (name "VCC1V8_AUX") (class "Default")
      (node (ref "C214") (pin "1") (pinfunction "1_1") (pintype "passive"))
      (node (ref "C215") (pin "1") (pinfunction "1_1") (pintype "passive"))
      (node (ref "C216") (pin "1") (pinfunction "1_1") (pintype "passive"))
      (node (ref "C233") (pin "1") (pinfunction "1_1") (pintype "passive"))
      (node (ref "C246") (pin "1") (pinfunction "1_1") (pintype "passive"))
      (node (ref "C269") (pin "1") (pinfunction "1_1") (pintype "passive"))
      (node (ref "C421") (pin "1") (pinfunction "1_1") (pintype "passive"))
      (node (ref "C422") (pin "1") (pinfunction "1_1") (pintype "passive"))
      (node (ref "U1") (pin "L11") (pinfunction "VCCAUX_L11") (pintype "power_in"))
      (node (ref "U1") (pin "M10") (pinfunction "VCCAUX_M10") (pintype "power_in"))
      (node (ref "U1") (pin "N6") (pinfunction "MGTVCCAUX_N6") (pintype "power_in"))
      (node (ref "U1") (pin "P10") (pinfunction "VCCAUX_P10") (pintype "power_in"))
      (node (ref "U1") (pin "P8") (pinfunction "VCCAUX_IO_G0_P8") (pintype "power_in"))
      (node (ref "U1") (pin "R9") (pinfunction "VCCAUX_IO_G0_R9") (pintype "power_in"))
      (node (ref "U1") (pin "T10") (pinfunction "VCCAUX_T10") (pintype "power_in"))
      (node (ref "U1") (pin "T8") (pinfunction "VCCAUX_IO_G0_T8") (pintype "power_in"))
      (node (ref "U1") (pin "U11") (pinfunction "VCCAUX_U11") (pintype "power_in"))
    )
    (net (code "10") (name "VCC2V5") (class "Default")
      (node (ref "C219") (pin "1") (pinfunction "1_1") (pintype "passive"))
      (node (ref "C226") (pin "1") (pinfunction "1_1") (pintype "passive"))
      (node (ref "C234") (pin "1") (pinfunction "1_1") (pintype "passive"))
      (node (ref "U1") (pin "L7") (pinfunction "VCCO_0_L7") (pintype "power_in"))
      (node (ref "U1") (pin "T6") (pinfunction "VCCO_0_T6") (pintype "power_in"))
    )
    (net (code "11") (name "VCC3V3") (class "Default")
      (node (ref "C205") (pin "1") (pinfunction "1_1") (pintype "passive"))
      (node (ref "C206") (pin "1") (pinfunction "1_1") (pintype "passive"))
      (node (ref "C207") (pin "1") (pinfunction "1_1") (pintype "passive"))
      (node (ref "C208") (pin "1") (pinfunction "1_1") (pintype "passive"))
      (node (ref "C217") (pin "1") (pinfunction "1_1") (pintype "passive"))
      (node (ref "C218") (pin "1") (pinfunction "1_1") (pintype "passive"))
      (node (ref "C225") (pin "1") (pinfunction "1_1") (pintype "passive"))
      (node (ref "C275") (pin "1") (pinfunction "1_1") (pintype "passive"))
      (node (ref "C277") (pin "1") (pinfunction "1_1") (pintype "passive"))
      (node (ref "U1") (pin "A11") (pinfunction "VCCO_16_A11") (pintype "power_in"))
      (node (ref "U1") (pin "B18") (pinfunction "VCCO_15_B18") (pintype "power_in"))
      (node (ref "U1") (pin "B8") (pinfunction "VCCO_16_B8") (pintype "power_in"))
      (node (ref "U1") (pin "C15") (pinfunction "VCCO_16_C15") (pintype "power_in"))
      (node (ref "U1") (pin "D12") (pinfunction "VCCO_16_D12") (pintype "power_in"))
      (node (ref "U1") (pin "E19") (pinfunction "VCCO_15_E19") (pintype "power_in"))
      (node (ref "U1") (pin "E9") (pinfunction "VCCO_16_E9") (pintype "power_in"))
      (node (ref "U1") (pin "F16") (pinfunction "VCCO_15_F16") (pintype "power_in"))
      (node (ref "U1") (pin "G13") (pinfunction "VCCO_16_G13") (pintype "power_in"))
      (node (ref "U1") (pin "H10") (pinfunction "VCCO_16_H10") (pintype "power_in"))
      (node (ref "U1") (pin "H20") (pinfunction "VCCO_15_H20") (pintype "power_in"))
      (node (ref "U1") (pin "J17") (pinfunction "VCCO_15_J17") (pintype "power_in"))
      (node (ref "U1") (pin "K24") (pinfunction "VCCO_13_K24") (pintype "power_in"))
      (node (ref "U1") (pin "M18") (pinfunction "VCCO_15_M18") (pintype "power_in"))
      (node (ref "U1") (pin "N25") (pinfunction "VCCO_13_N25") (pintype "power_in"))
      (node (ref "U1") (pin "P22") (pinfunction "VCCO_13_P22") (pintype "power_in"))
      (node (ref "U1") (pin "R19") (pinfunction "VCCO_13_R19") (pintype "power_in"))
      (node (ref "U1") (pin "T16") (pinfunction "VCCO_13_T16") (pintype "power_in"))
      (node (ref "U1") (pin "T26") (pinfunction "VCCO_13_T26") (pintype "power_in"))
    )
  )
)
